# Shapeoko_Controller.net
KiCad netlist of a schematic drawn in EAGLE
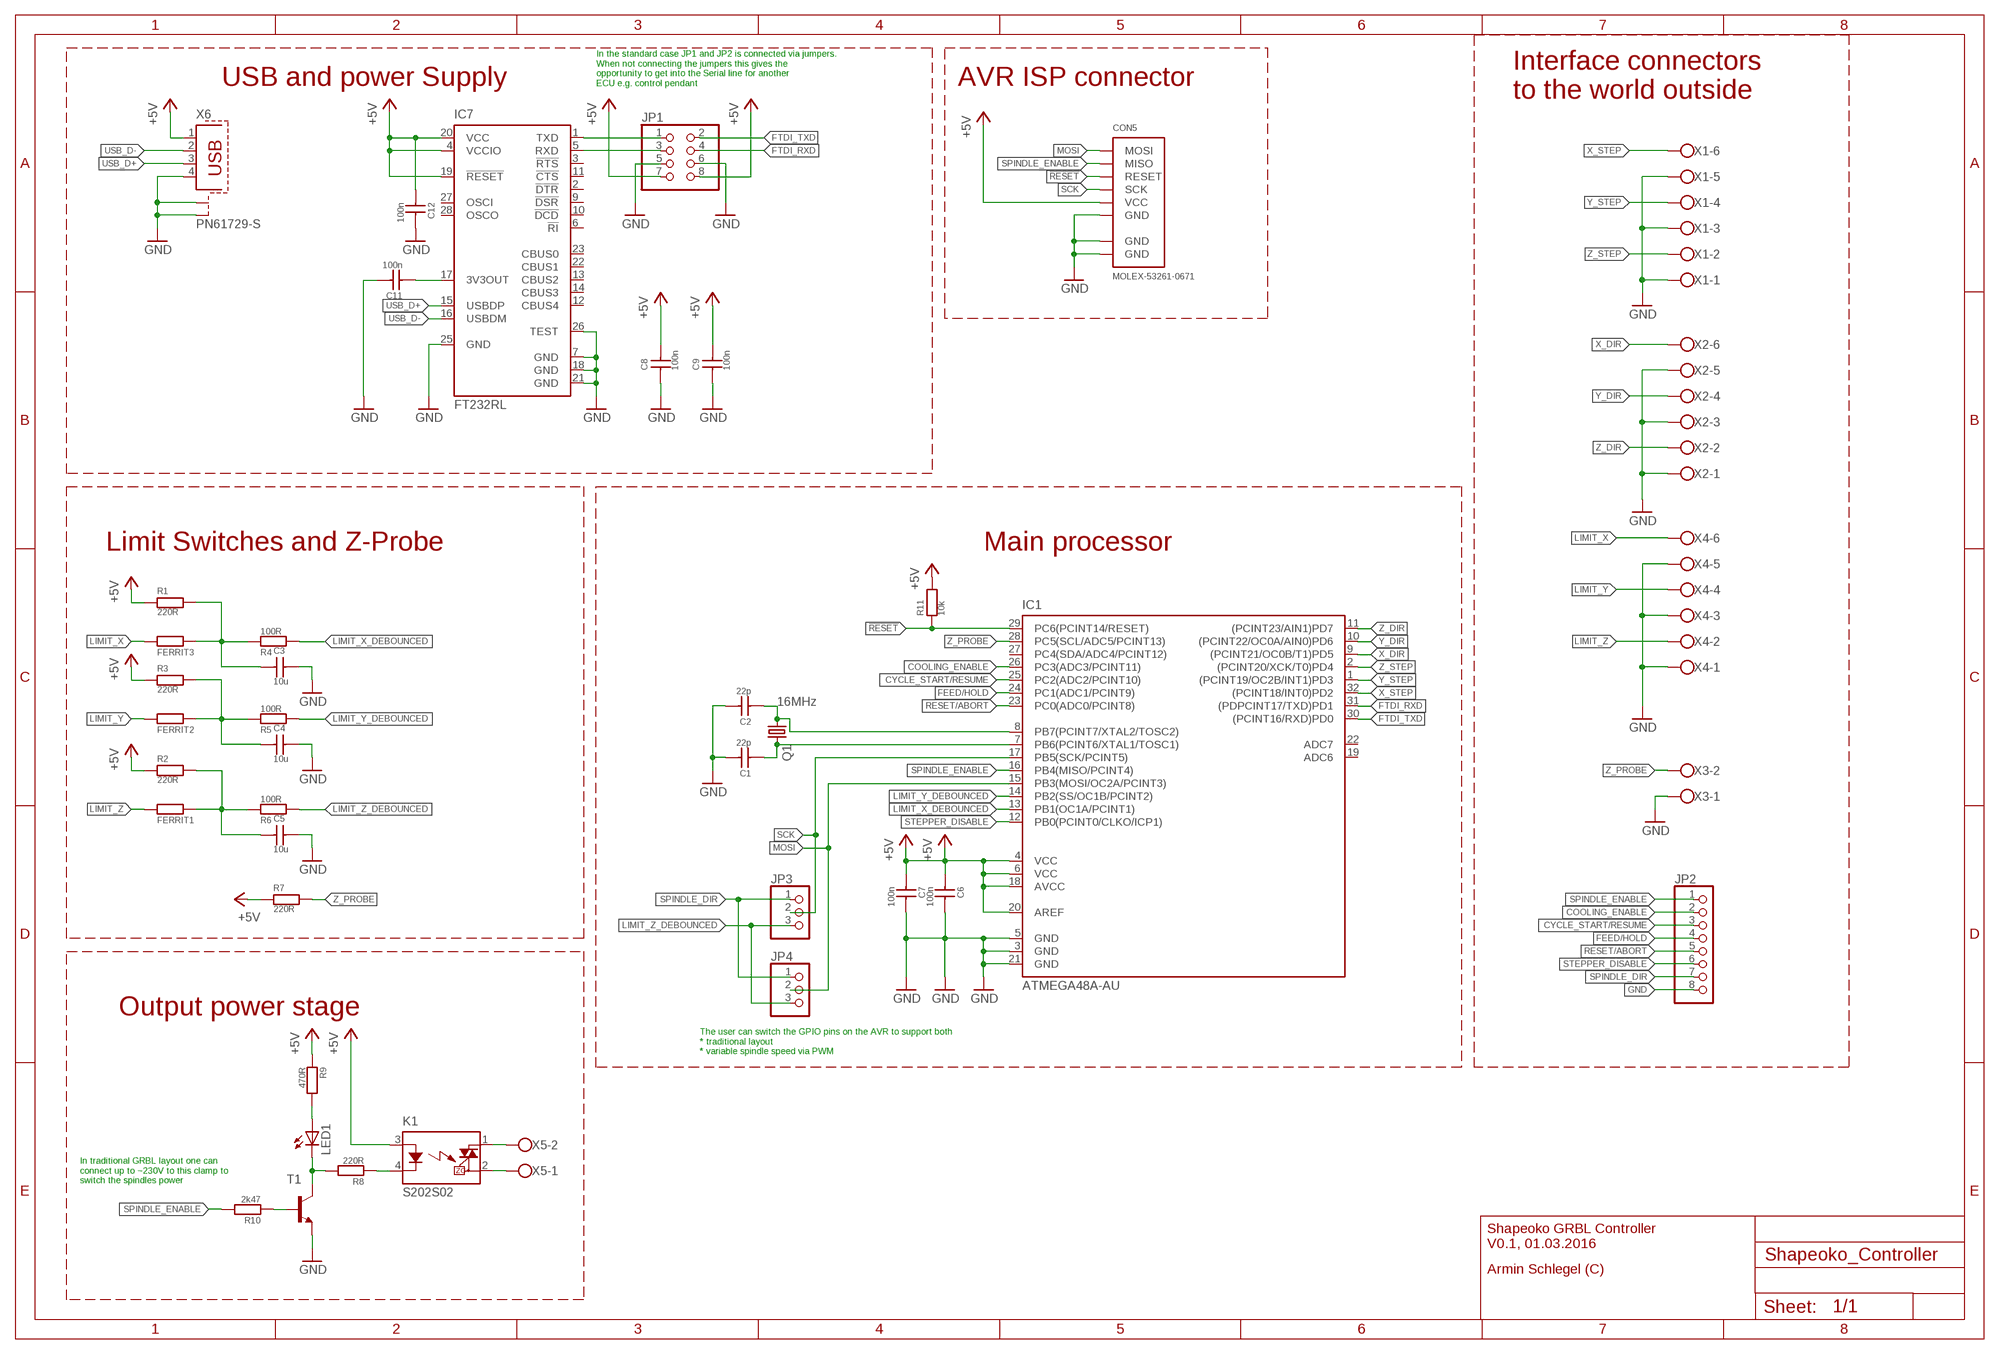
[diagram p0: schematic, sheet 1]

(export (version "E")
  (design (tool "Eeschema 10.0.6"))
  (components
    (comp (ref "C1")
      (value "22p")
      (footprint "eagle-import:C0603")
      (libsource (lib "eagle-import") (part "C_SMD0603"))
    )
    (comp (ref "C2")
      (value "22p")
      (footprint "eagle-import:C0603")
      (libsource (lib "eagle-import") (part "C_SMD0603"))
    )
    (comp (ref "C3")
      (value "10u")
      (footprint "eagle-import:C0805")
      (libsource (lib "eagle-import") (part "C_SMD0805"))
    )
    (comp (ref "C4")
      (value "10u")
      (footprint "eagle-import:C0805")
      (libsource (lib "eagle-import") (part "C_SMD0805"))
    )
    (comp (ref "C5")
      (value "10u")
      (footprint "eagle-import:C0805")
      (libsource (lib "eagle-import") (part "C_SMD0805"))
    )
    (comp (ref "C6")
      (value "100n")
      (footprint "eagle-import:C0603")
      (libsource (lib "eagle-import") (part "C_SMD0603"))
    )
    (comp (ref "C7")
      (value "100n")
      (footprint "eagle-import:C0603")
      (libsource (lib "eagle-import") (part "C_SMD0603"))
    )
    (comp (ref "C8")
      (value "100n")
      (footprint "eagle-import:C0603")
      (libsource (lib "eagle-import") (part "C_SMD0603"))
    )
    (comp (ref "C9")
      (value "100n")
      (footprint "eagle-import:C0603")
      (libsource (lib "eagle-import") (part "C_SMD0603"))
    )
    (comp (ref "C11")
      (value "100n")
      (footprint "eagle-import:C0603")
      (libsource (lib "eagle-import") (part "C_SMD0603"))
    )
    (comp (ref "C12")
      (value "100n")
      (footprint "eagle-import:C0603")
      (libsource (lib "eagle-import") (part "C_SMD0603"))
    )
    (comp (ref "CON5")
      (value "MOLEX-53261-0671")
      (footprint "eagle-import:MOLEX-53261-0671")
      (libsource (lib "eagle-import") (part "MOLEX-53261-0671"))
    )
    (comp (ref "FERRIT1")
      (value "R0805")
      (footprint "eagle-import:R0805")
      (libsource (lib "eagle-import") (part "R0805"))
    )
    (comp (ref "FERRIT2")
      (value "R0805")
      (footprint "eagle-import:R0805")
      (libsource (lib "eagle-import") (part "R0805"))
    )
    (comp (ref "FERRIT3")
      (value "R0805")
      (footprint "eagle-import:R0805")
      (libsource (lib "eagle-import") (part "R0805"))
    )
    (comp (ref "IC1")
      (value "ATMEGA48A-AU")
      (footprint "eagle-import:TQFP32")
      (libsource (lib "eagle-import") (part "ATMEGA48A-AU"))
    )
    (comp (ref "IC7")
      (value "FT232RL")
      (footprint "eagle-import:SSOP28")
      (libsource (lib "eagle-import") (part "FT232RL"))
    )
    (comp (ref "JP1")
      (value "PINHD-2X4")
      (footprint "eagle-import:2X04")
      (libsource (lib "eagle-import") (part "PINHD-2X4"))
    )
    (comp (ref "JP2")
      (value "PINHD-1X8")
      (footprint "eagle-import:1X08")
      (libsource (lib "eagle-import") (part "PINHD-1X8"))
    )
    (comp (ref "JP3")
      (value "PINHD-1X3")
      (footprint "eagle-import:1X03")
      (libsource (lib "eagle-import") (part "PINHD-1X3"))
    )
    (comp (ref "JP4")
      (value "PINHD-1X3")
      (footprint "eagle-import:1X03")
      (libsource (lib "eagle-import") (part "PINHD-1X3"))
    )
    (comp (ref "K1")
      (value "S202S02")
      (footprint "eagle-import:S202S02")
      (fields (field (name "MPN") "S202S02F"))
      (libsource (lib "eagle-import") (part "S02S022"))
    )
    (comp (ref "LED1")
      (value "LED3MM")
      (footprint "eagle-import:LED3MM")
      (libsource (lib "eagle-import") (part "LED3MM"))
    )
    (comp (ref "Q1")
      (value "16MHz")
      (footprint "eagle-import:HC49UP")
      (libsource (lib "eagle-import") (part "CRYSTALHC49UP"))
    )
    (comp (ref "R1")
      (value "220R")
      (footprint "eagle-import:R0603")
      (libsource (lib "eagle-import") (part "R0603"))
    )
    (comp (ref "R2")
      (value "220R")
      (footprint "eagle-import:R0603")
      (libsource (lib "eagle-import") (part "R0603"))
    )
    (comp (ref "R3")
      (value "220R")
      (footprint "eagle-import:R0603")
      (libsource (lib "eagle-import") (part "R0603"))
    )
    (comp (ref "R4")
      (value "100R")
      (footprint "eagle-import:R0603")
      (libsource (lib "eagle-import") (part "R0603"))
    )
    (comp (ref "R5")
      (value "100R")
      (footprint "eagle-import:R0603")
      (libsource (lib "eagle-import") (part "R0603"))
    )
    (comp (ref "R6")
      (value "100R")
      (footprint "eagle-import:R0603")
      (libsource (lib "eagle-import") (part "R0603"))
    )
    (comp (ref "R7")
      (value "220R")
      (footprint "eagle-import:R0603")
      (libsource (lib "eagle-import") (part "R0603"))
    )
    (comp (ref "R8")
      (value "220R")
      (footprint "eagle-import:R0603")
      (libsource (lib "eagle-import") (part "R0603"))
    )
    (comp (ref "R9")
      (value "470R")
      (footprint "eagle-import:R0603")
      (libsource (lib "eagle-import") (part "R0603"))
    )
    (comp (ref "R10")
      (value "2k47")
      (footprint "eagle-import:R0603")
      (libsource (lib "eagle-import") (part "R0603"))
    )
    (comp (ref "R11")
      (value "10k")
      (footprint "eagle-import:R0603")
      (libsource (lib "eagle-import") (part "R0603"))
    )
    (comp (ref "T1")
      (value "BC847-NPN-SOT23-BEC")
      (footprint "eagle-import:SOT23-BEC")
      (libsource (lib "eagle-import") (part "-NPN-SOT23-BECBC847"))
    )
    (comp (ref "X1")
      (value "W237-136")
      (footprint "eagle-import:W237-136")
      (fields (field (name "MPN") "237-136"))
      (libsource (lib "eagle-import") (part "W237-136"))
    )
    (comp (ref "X2")
      (value "W237-136")
      (footprint "eagle-import:W237-136")
      (fields (field (name "MPN") "237-136"))
      (libsource (lib "eagle-import") (part "W237-136"))
    )
    (comp (ref "X3")
      (value "W237-102")
      (footprint "eagle-import:W237-102")
      (fields (field (name "MPN") "237-102"))
      (libsource (lib "eagle-import") (part "W237-102"))
    )
    (comp (ref "X4")
      (value "W237-136")
      (footprint "eagle-import:W237-136")
      (fields (field (name "MPN") "237-136"))
      (libsource (lib "eagle-import") (part "W237-136"))
    )
    (comp (ref "X5")
      (value "W237-102")
      (footprint "eagle-import:W237-102")
      (fields (field (name "MPN") "237-102"))
      (libsource (lib "eagle-import") (part "W237-102"))
    )
    (comp (ref "X6")
      (value "PN61729-S")
      (footprint "eagle-import:PN61729-S")
      (libsource (lib "eagle-import") (part "PN61729-S"))
    )
  )
  (nets
    (net (code "1") (name "+5V") (class "Default")
      (node (ref "C12") (pin "1") (pinfunction "P$1_1") (pintype "passive"))
      (node (ref "C6") (pin "1") (pinfunction "P$1_1") (pintype "passive"))
      (node (ref "C7") (pin "1") (pinfunction "P$1_1") (pintype "passive"))
      (node (ref "C8") (pin "2") (pinfunction "P$2_2") (pintype "passive"))
      (node (ref "C9") (pin "2") (pinfunction "P$2_2") (pintype "passive"))
      (node (ref "CON5") (pin "5") (pinfunction "VCC_5") (pintype "bidirectional"))
      (node (ref "IC1") (pin "18") (pinfunction "AVCC_18") (pintype "power_in"))
      (node (ref "IC1") (pin "20") (pinfunction "AREF_20") (pintype "power_in"))
      (node (ref "IC1") (pin "4") (pinfunction "VCC_4") (pintype "power_in"))
      (node (ref "IC1") (pin "6") (pinfunction "VCC_6") (pintype "power_in"))
      (node (ref "IC7") (pin "19") (pinfunction "~{RESET}_19") (pintype "input"))
      (node (ref "IC7") (pin "20") (pinfunction "VCC_20") (pintype "power_in"))
      (node (ref "IC7") (pin "4") (pinfunction "VCCIO_4") (pintype "power_in"))
      (node (ref "JP1") (pin "7") (pinfunction "7_7") (pintype "passive"))
      (node (ref "JP1") (pin "8") (pinfunction "8_8") (pintype "passive"))
      (node (ref "K1") (pin "3") (pinfunction "A_3") (pintype "passive"))
      (node (ref "R1") (pin "1") (pinfunction "P$1_1") (pintype "passive"))
      (node (ref "R11") (pin "2") (pinfunction "P$2_2") (pintype "passive"))
      (node (ref "R2") (pin "1") (pinfunction "P$1_1") (pintype "passive"))
      (node (ref "R3") (pin "1") (pinfunction "P$1_1") (pintype "passive"))
      (node (ref "R7") (pin "1") (pinfunction "P$1_1") (pintype "passive"))
      (node (ref "R9") (pin "1") (pinfunction "P$1_1") (pintype "passive"))
      (node (ref "X6") (pin "1") (pinfunction "1_1") (pintype "passive"))
    )
    (net (code "2") (name "/~{RESET}") (class "Default")
      (node (ref "CON5") (pin "3") (pinfunction "RESET_3") (pintype "bidirectional"))
      (node (ref "IC1") (pin "29") (pinfunction "PC6(PCINT14/RESET)_29") (pintype "bidirectional"))
      (node (ref "R11") (pin "1") (pinfunction "P$1_1") (pintype "passive"))
    )
    (net (code "3") (name "COOLING_ENABLE") (class "Default")
      (node (ref "IC1") (pin "26") (pinfunction "PC3(ADC3/PCINT11)_26") (pintype "bidirectional"))
      (node (ref "JP2") (pin "2") (pinfunction "2_2") (pintype "passive"))
    )
    (net (code "4") (name "CYCLE_START{slash}RESUME") (class "Default")
      (node (ref "IC1") (pin "25") (pinfunction "PC2(ADC2/PCINT10)_25") (pintype "bidirectional"))
      (node (ref "JP2") (pin "3") (pinfunction "3_3") (pintype "passive"))
    )
    (net (code "5") (name "FEED{slash}HOLD") (class "Default")
      (node (ref "IC1") (pin "24") (pinfunction "PC1(ADC1/PCINT9)_24") (pintype "bidirectional"))
      (node (ref "JP2") (pin "4") (pinfunction "4_4") (pintype "passive"))
    )
    (net (code "6") (name "FTDI_RXD") (class "Default")
      (node (ref "IC1") (pin "31") (pinfunction "(PDPCINT17/TXD)PD1_31") (pintype "bidirectional"))
      (node (ref "JP1") (pin "4") (pinfunction "4_4") (pintype "passive"))
    )
    (net (code "7") (name "FTDI_TXD") (class "Default")
      (node (ref "IC1") (pin "30") (pinfunction "(PCINT16/RXD)PD0_30") (pintype "bidirectional"))
      (node (ref "JP1") (pin "2") (pinfunction "2_2") (pintype "passive"))
    )
    (net (code "8") (name "GND") (class "Default")
      (node (ref "C1") (pin "2") (pinfunction "P$2_2") (pintype "passive"))
      (node (ref "C11") (pin "2") (pinfunction "P$2_2") (pintype "passive"))
      (node (ref "C12") (pin "2") (pinfunction "P$2_2") (pintype "passive"))
      (node (ref "C2") (pin "2") (pinfunction "P$2_2") (pintype "passive"))
      (node (ref "C3") (pin "2") (pinfunction "P$2_2") (pintype "passive"))
      (node (ref "C4") (pin "2") (pinfunction "P$2_2") (pintype "passive"))
      (node (ref "C5") (pin "2") (pinfunction "P$2_2") (pintype "passive"))
      (node (ref "C6") (pin "2") (pinfunction "P$2_2") (pintype "passive"))
      (node (ref "C7") (pin "2") (pinfunction "P$2_2") (pintype "passive"))
      (node (ref "C8") (pin "1") (pinfunction "P$1_1") (pintype "passive"))
      (node (ref "C9") (pin "1") (pinfunction "P$1_1") (pintype "passive"))
      (node (ref "CON5") (pin "6") (pinfunction "GND_6") (pintype "bidirectional"))
      (node (ref "CON5") (pin "GND@1") (pinfunction "GND_GND@1") (pintype "power_in"))
      (node (ref "CON5") (pin "GND@2") (pinfunction "GND_GND@2") (pintype "power_in"))
      (node (ref "IC1") (pin "21") (pinfunction "GND_21") (pintype "power_in"))
      (node (ref "IC1") (pin "3") (pinfunction "GND_3") (pintype "power_in"))
      (node (ref "IC1") (pin "5") (pinfunction "GND_5") (pintype "power_in"))
      (node (ref "IC7") (pin "18") (pinfunction "GND_18") (pintype "power_in"))
      (node (ref "IC7") (pin "21") (pinfunction "GND_21") (pintype "power_in"))
      (node (ref "IC7") (pin "25") (pinfunction "GND_25") (pintype "power_in"))
      (node (ref "IC7") (pin "26") (pinfunction "TEST_26") (pintype "input"))
      (node (ref "IC7") (pin "7") (pinfunction "GND_7") (pintype "power_in"))
      (node (ref "JP1") (pin "5") (pinfunction "5_5") (pintype "passive"))
      (node (ref "JP1") (pin "6") (pinfunction "6_6") (pintype "passive"))
      (node (ref "JP2") (pin "8") (pinfunction "8_8") (pintype "passive"))
      (node (ref "T1") (pin "E") (pinfunction "E_E") (pintype "passive"))
      (node (ref "X1") (pin "1") (pinfunction "KL_1") (pintype "passive"))
      (node (ref "X1") (pin "3") (pinfunction "KL_3") (pintype "passive"))
      (node (ref "X1") (pin "5") (pinfunction "KL_5") (pintype "passive"))
      (node (ref "X2") (pin "1") (pinfunction "KL_1") (pintype "passive"))
      (node (ref "X2") (pin "3") (pinfunction "KL_3") (pintype "passive"))
      (node (ref "X2") (pin "5") (pinfunction "KL_5") (pintype "passive"))
      (node (ref "X3") (pin "1") (pinfunction "KL_1") (pintype "passive"))
      (node (ref "X4") (pin "1") (pinfunction "KL_1") (pintype "passive"))
      (node (ref "X4") (pin "3") (pinfunction "KL_3") (pintype "passive"))
      (node (ref "X4") (pin "5") (pinfunction "KL_5") (pintype "passive"))
      (node (ref "X6") (pin "4") (pinfunction "4_4") (pintype "passive"))
      (node (ref "X6") (pin "S1") (pinfunction "S1_S1") (pintype "passive"))
      (node (ref "X6") (pin "S2") (pinfunction "S2_S2") (pintype "passive"))
    )
    (net (code "9") (name "LIMIT_X") (class "Default")
      (node (ref "FERRIT3") (pin "1") (pinfunction "P$1_1") (pintype "passive"))
      (node (ref "X4") (pin "6") (pinfunction "KL_6") (pintype "passive"))
    )
    (net (code "10") (name "LIMIT_X_DEBOUNCED") (class "Default")
      (node (ref "IC1") (pin "13") (pinfunction "PB1(OC1A/PCINT1)_13") (pintype "bidirectional"))
      (node (ref "R4") (pin "2") (pinfunction "P$2_2") (pintype "passive"))
    )
    (net (code "11") (name "LIMIT_Y") (class "Default")
      (node (ref "FERRIT2") (pin "1") (pinfunction "P$1_1") (pintype "passive"))
      (node (ref "X4") (pin "4") (pinfunction "KL_4") (pintype "passive"))
    )
    (net (code "12") (name "LIMIT_Y_DEBOUNCED") (class "Default")
      (node (ref "IC1") (pin "14") (pinfunction "PB2(SS/OC1B/PCINT2)_14") (pintype "bidirectional"))
      (node (ref "R5") (pin "2") (pinfunction "P$2_2") (pintype "passive"))
    )
    (net (code "13") (name "LIMIT_Z") (class "Default")
      (node (ref "FERRIT1") (pin "1") (pinfunction "P$1_1") (pintype "passive"))
      (node (ref "X4") (pin "2") (pinfunction "KL_2") (pintype "passive"))
    )
    (net (code "14") (name "LIMIT_Z_DEBOUNCED") (class "Default")
      (node (ref "JP3") (pin "3") (pinfunction "3_3") (pintype "passive"))
      (node (ref "JP4") (pin "3") (pinfunction "3_3") (pintype "passive"))
      (node (ref "R6") (pin "2") (pinfunction "P$2_2") (pintype "passive"))
    )
    (net (code "15") (name "MOSI") (class "Default")
      (node (ref "CON5") (pin "1") (pinfunction "MOSI_1") (pintype "bidirectional"))
      (node (ref "IC1") (pin "15") (pinfunction "PB3(MOSI/OC2A/PCINT3)_15") (pintype "bidirectional"))
      (node (ref "JP4") (pin "2") (pinfunction "2_2") (pintype "passive"))
    )
    (net (code "16") (name "Net-(C1-P$1)") (class "Default")
      (node (ref "C1") (pin "1") (pinfunction "P$1_1") (pintype "passive"))
      (node (ref "IC1") (pin "7") (pinfunction "PB6(PCINT6/XTAL1/TOSC1)_7") (pintype "bidirectional"))
      (node (ref "Q1") (pin "2") (pinfunction "2_2") (pintype "passive"))
    )
    (net (code "17") (name "Net-(C2-P$1)") (class "Default")
      (node (ref "C2") (pin "1") (pinfunction "P$1_1") (pintype "passive"))
      (node (ref "IC1") (pin "8") (pinfunction "PB7(PCINT7/XTAL2/TOSC2)_8") (pintype "bidirectional"))
      (node (ref "Q1") (pin "1") (pinfunction "1_1") (pintype "passive"))
    )
    (net (code "18") (name "Net-(C3-P$1)") (class "Default")
      (node (ref "C3") (pin "1") (pinfunction "P$1_1") (pintype "passive"))
      (node (ref "FERRIT3") (pin "2") (pinfunction "P$2_2") (pintype "passive"))
      (node (ref "R1") (pin "2") (pinfunction "P$2_2") (pintype "passive"))
      (node (ref "R4") (pin "1") (pinfunction "P$1_1") (pintype "passive"))
    )
    (net (code "19") (name "Net-(C4-P$1)") (class "Default")
      (node (ref "C4") (pin "1") (pinfunction "P$1_1") (pintype "passive"))
      (node (ref "FERRIT2") (pin "2") (pinfunction "P$2_2") (pintype "passive"))
      (node (ref "R3") (pin "2") (pinfunction "P$2_2") (pintype "passive"))
      (node (ref "R5") (pin "1") (pinfunction "P$1_1") (pintype "passive"))
    )
    (net (code "20") (name "Net-(C5-P$1)") (class "Default")
      (node (ref "C5") (pin "1") (pinfunction "P$1_1") (pintype "passive"))
      (node (ref "FERRIT1") (pin "2") (pinfunction "P$2_2") (pintype "passive"))
      (node (ref "R2") (pin "2") (pinfunction "P$2_2") (pintype "passive"))
      (node (ref "R6") (pin "1") (pinfunction "P$1_1") (pintype "passive"))
    )
    (net (code "21") (name "Net-(C11-P$1)") (class "Default")
      (node (ref "C11") (pin "1") (pinfunction "P$1_1") (pintype "passive"))
      (node (ref "IC7") (pin "17") (pinfunction "3V3OUT_17") (pintype "output"))
    )
    (net (code "22") (name "Net-(IC7-RXD)") (class "Default")
      (node (ref "IC7") (pin "5") (pinfunction "RXD_5") (pintype "input"))
      (node (ref "JP1") (pin "3") (pinfunction "3_3") (pintype "passive"))
    )
    (net (code "23") (name "Net-(IC7-TXD)") (class "Default")
      (node (ref "IC7") (pin "1") (pinfunction "TXD_1") (pintype "output"))
      (node (ref "JP1") (pin "1") (pinfunction "1_1") (pintype "passive"))
    )
    (net (code "24") (name "Net-(K1-DS1)") (class "Default")
      (node (ref "K1") (pin "1") (pinfunction "DS1_1") (pintype "passive"))
      (node (ref "X5") (pin "2") (pinfunction "KL_2") (pintype "passive"))
    )
    (net (code "25") (name "Net-(K1-DS2)") (class "Default")
      (node (ref "K1") (pin "2") (pinfunction "DS2_2") (pintype "passive"))
      (node (ref "X5") (pin "1") (pinfunction "KL_1") (pintype "passive"))
    )
    (net (code "26") (name "Net-(K1-K)") (class "Default")
      (node (ref "K1") (pin "4") (pinfunction "K_4") (pintype "passive"))
      (node (ref "R8") (pin "1") (pinfunction "P$1_1") (pintype "passive"))
    )
    (net (code "27") (name "Net-(LED1-C)") (class "Default")
      (node (ref "LED1") (pin "K") (pinfunction "C_K") (pintype "passive"))
      (node (ref "R8") (pin "2") (pinfunction "P$2_2") (pintype "passive"))
      (node (ref "T1") (pin "C") (pinfunction "C_C") (pintype "passive"))
    )
    (net (code "28") (name "Net-(R9-P$2)") (class "Default")
      (node (ref "LED1") (pin "A") (pinfunction "A_A") (pintype "passive"))
      (node (ref "R9") (pin "2") (pinfunction "P$2_2") (pintype "passive"))
    )
    (net (code "29") (name "Net-(R10-P$1)") (class "Default")
      (node (ref "R10") (pin "1") (pinfunction "P$1_1") (pintype "passive"))
      (node (ref "T1") (pin "B") (pinfunction "B_B") (pintype "passive"))
    )
    (net (code "30") (name "RESET{slash}ABORT") (class "Default")
      (node (ref "IC1") (pin "23") (pinfunction "PC0(ADC0/PCINT8)_23") (pintype "bidirectional"))
      (node (ref "JP2") (pin "5") (pinfunction "5_5") (pintype "passive"))
    )
    (net (code "31") (name "SCK") (class "Default")
      (node (ref "CON5") (pin "4") (pinfunction "SCK_4") (pintype "bidirectional"))
      (node (ref "IC1") (pin "17") (pinfunction "PB5(SCK/PCINT5)_17") (pintype "bidirectional"))
      (node (ref "JP3") (pin "2") (pinfunction "2_2") (pintype "passive"))
    )
    (net (code "32") (name "SPINDLE_DIR") (class "Default")
      (node (ref "JP2") (pin "7") (pinfunction "7_7") (pintype "passive"))
      (node (ref "JP3") (pin "1") (pinfunction "1_1") (pintype "passive"))
      (node (ref "JP4") (pin "1") (pinfunction "1_1") (pintype "passive"))
    )
    (net (code "33") (name "SPINDLE_ENABLE") (class "Default")
      (node (ref "CON5") (pin "2") (pinfunction "MISO_2") (pintype "bidirectional"))
      (node (ref "IC1") (pin "16") (pinfunction "PB4(MISO/PCINT4)_16") (pintype "bidirectional"))
      (node (ref "JP2") (pin "1") (pinfunction "1_1") (pintype "passive"))
      (node (ref "R10") (pin "2") (pinfunction "P$2_2") (pintype "passive"))
    )
    (net (code "34") (name "STEPPER_DISABLE") (class "Default")
      (node (ref "IC1") (pin "12") (pinfunction "PB0(PCINT0/CLKO/ICP1)_12") (pintype "bidirectional"))
      (node (ref "JP2") (pin "6") (pinfunction "6_6") (pintype "passive"))
    )
    (net (code "35") (name "USB_D+") (class "Default")
      (node (ref "IC7") (pin "15") (pinfunction "USBDP_15") (pintype "bidirectional"))
      (node (ref "X6") (pin "3") (pinfunction "3_3") (pintype "passive"))
    )
    (net (code "36") (name "USB_D-") (class "Default")
      (node (ref "IC7") (pin "16") (pinfunction "USBDM_16") (pintype "bidirectional"))
      (node (ref "X6") (pin "2") (pinfunction "2_2") (pintype "passive"))
    )
    (net (code "37") (name "X_DIR") (class "Default")
      (node (ref "IC1") (pin "9") (pinfunction "(PCINT21/OC0B/T1)PD5_9") (pintype "bidirectional"))
      (node (ref "X2") (pin "6") (pinfunction "KL_6") (pintype "passive"))
    )
    (net (code "38") (name "X_STEP") (class "Default")
      (node (ref "IC1") (pin "32") (pinfunction "(PCINT18/INT0)PD2_32") (pintype "bidirectional"))
      (node (ref "X1") (pin "6") (pinfunction "KL_6") (pintype "passive"))
    )
    (net (code "39") (name "Y_DIR") (class "Default")
      (node (ref "IC1") (pin "10") (pinfunction "(PCINT22/OC0A/AIN0)PD6_10") (pintype "bidirectional"))
      (node (ref "X2") (pin "4") (pinfunction "KL_4") (pintype "passive"))
    )
    (net (code "40") (name "Y_STEP") (class "Default")
      (node (ref "IC1") (pin "1") (pinfunction "(PCINT19/OC2B/INT1)PD3_1") (pintype "bidirectional"))
      (node (ref "X1") (pin "4") (pinfunction "KL_4") (pintype "passive"))
    )
    (net (code "41") (name "Z_DIR") (class "Default")
      (node (ref "IC1") (pin "11") (pinfunction "(PCINT23/AIN1)PD7_11") (pintype "bidirectional"))
      (node (ref "X2") (pin "2") (pinfunction "KL_2") (pintype "passive"))
    )
    (net (code "42") (name "Z_PROBE") (class "Default")
      (node (ref "IC1") (pin "28") (pinfunction "PC5(SCL/ADC5/PCINT13)_28") (pintype "bidirectional"))
      (node (ref "R7") (pin "2") (pinfunction "P$2_2") (pintype "passive"))
      (node (ref "X3") (pin "2") (pinfunction "KL_2") (pintype "passive"))
    )
    (net (code "43") (name "Z_STEP") (class "Default")
      (node (ref "IC1") (pin "2") (pinfunction "(PCINT20/XCK/T0)PD4_2") (pintype "bidirectional"))
      (node (ref "X1") (pin "2") (pinfunction "KL_2") (pintype "passive"))
    )
    (net (code "44") (name "unconnected-(IC1-ADC6-Pad19)") (class "Default")
      (node (ref "IC1") (pin "19") (pinfunction "ADC6_19") (pintype "bidirectional"))
    )
    (net (code "45") (name "unconnected-(IC1-ADC7-Pad22)") (class "Default")
      (node (ref "IC1") (pin "22") (pinfunction "ADC7_22") (pintype "bidirectional"))
    )
    (net (code "46") (name "unconnected-(IC1-PC4(SDA{slash}ADC4{slash}PCINT12)-Pad27)") (class "Default")
      (node (ref "IC1") (pin "27") (pinfunction "PC4(SDA/ADC4/PCINT12)_27") (pintype "bidirectional"))
    )
    (net (code "47") (name "unconnected-(IC7-CBUS0-Pad23)") (class "Default")
      (node (ref "IC7") (pin "23") (pinfunction "CBUS0_23") (pintype "bidirectional"))
    )
    (net (code "48") (name "unconnected-(IC7-CBUS1-Pad22)") (class "Default")
      (node (ref "IC7") (pin "22") (pinfunction "CBUS1_22") (pintype "bidirectional"))
    )
    (net (code "49") (name "unconnected-(IC7-CBUS2-Pad13)") (class "Default")
      (node (ref "IC7") (pin "13") (pinfunction "CBUS2_13") (pintype "bidirectional"))
    )
    (net (code "50") (name "unconnected-(IC7-CBUS3-Pad14)") (class "Default")
      (node (ref "IC7") (pin "14") (pinfunction "CBUS3_14") (pintype "bidirectional"))
    )
    (net (code "51") (name "unconnected-(IC7-CBUS4-Pad12)") (class "Default")
      (node (ref "IC7") (pin "12") (pinfunction "CBUS4_12") (pintype "bidirectional"))
    )
    (net (code "52") (name "unconnected-(IC7-OSCI-Pad27)") (class "Default")
      (node (ref "IC7") (pin "27") (pinfunction "OSCI_27") (pintype "input"))
    )
    (net (code "53") (name "unconnected-(IC7-OSCO-Pad28)") (class "Default")
      (node (ref "IC7") (pin "28") (pinfunction "OSCO_28") (pintype "output"))
    )
    (net (code "54") (name "unconnected-(IC7-~{CTS}-Pad11)") (class "Default")
      (node (ref "IC7") (pin "11") (pinfunction "~{CTS}_11") (pintype "input"))
    )
    (net (code "55") (name "unconnected-(IC7-~{DCD}-Pad10)") (class "Default")
      (node (ref "IC7") (pin "10") (pinfunction "~{DCD}_10") (pintype "input"))
    )
    (net (code "56") (name "unconnected-(IC7-~{DSR}-Pad9)") (class "Default")
      (node (ref "IC7") (pin "9") (pinfunction "~{DSR}_9") (pintype "input"))
    )
    (net (code "57") (name "unconnected-(IC7-~{DTR}-Pad2)") (class "Default")
      (node (ref "IC7") (pin "2") (pinfunction "~{DTR}_2") (pintype "output"))
    )
    (net (code "58") (name "unconnected-(IC7-~{RI}-Pad6)") (class "Default")
      (node (ref "IC7") (pin "6") (pinfunction "~{RI}_6") (pintype "input"))
    )
    (net (code "59") (name "unconnected-(IC7-~{RTS}-Pad3)") (class "Default")
      (node (ref "IC7") (pin "3") (pinfunction "~{RTS}_3") (pintype "output"))
    )
  )
)
